# FPGA_HDMI_IN_OUT.net
KiCad netlist of a schematic drawn in Altium Designer
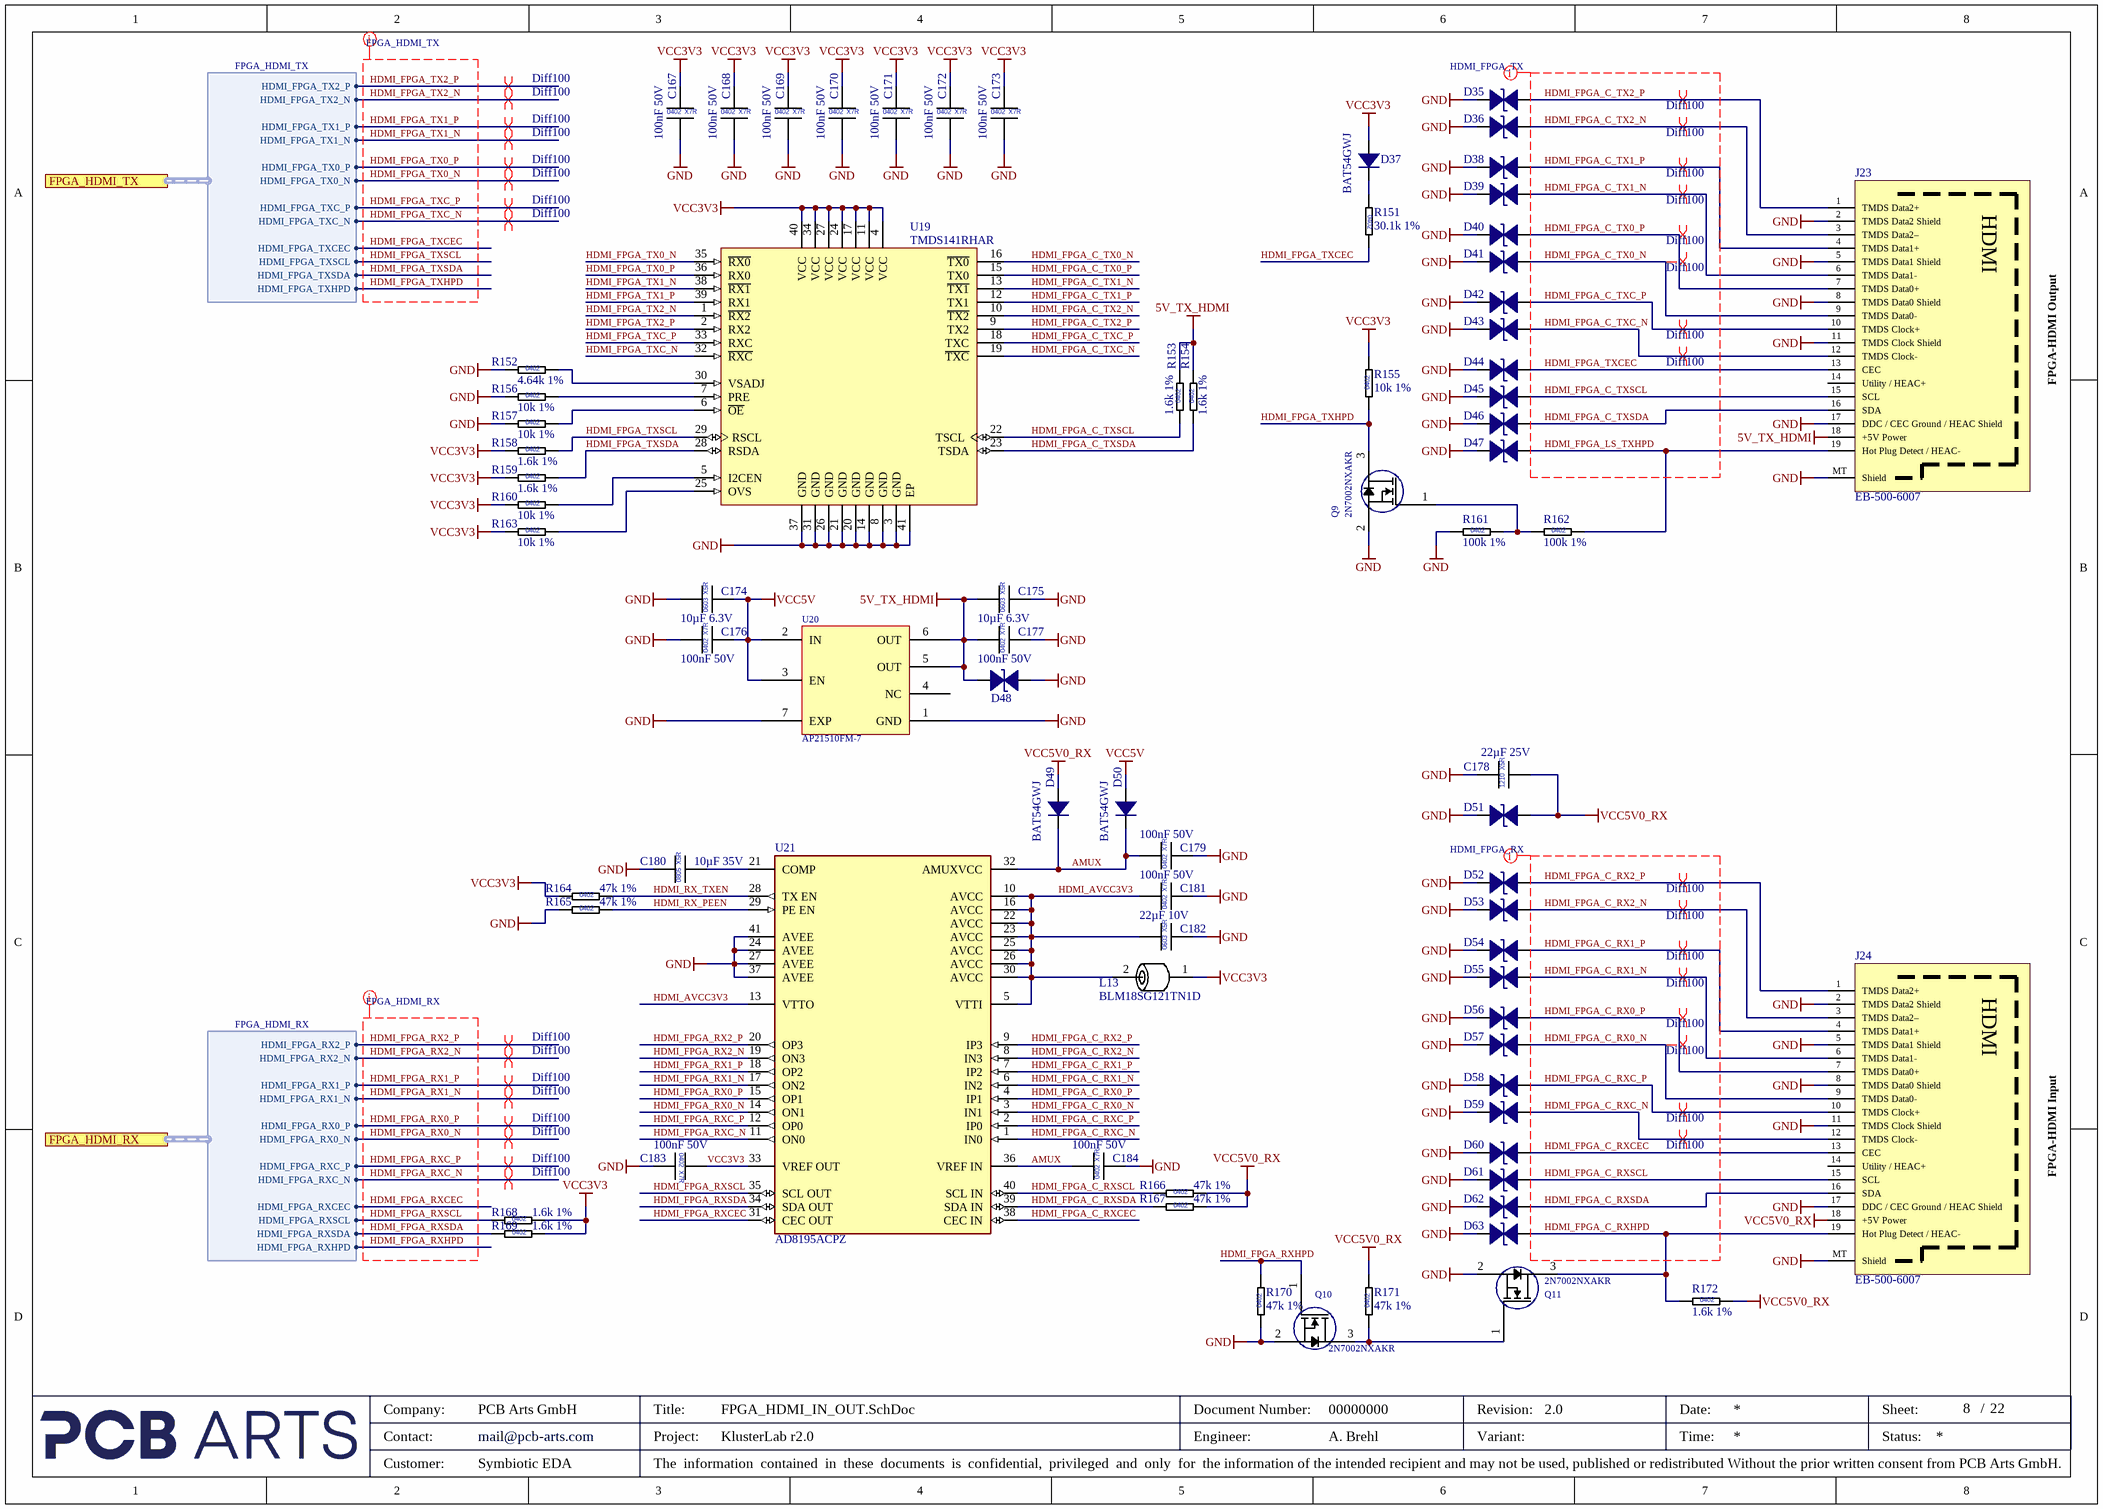
[diagram p0: FPGA_HDMI_IN_OUT.SchDoc]

(export (version "E")
  (design (tool "Eeschema 10.0.6"))
  (components
    (comp (ref "C167")
      (value "100nF 50V")
      (footprint "Cap:CAP_0402_L")
      (description "Multilayer Ceramic Capacitors MLCC - SMD/SMT 0402 50VDC")
      (libsource (lib "") (part "CAP_0402_100nF_50V_1"))
    )
    (comp (ref "C168")
      (value "100nF 50V")
      (footprint "Cap:CAP_0402_L")
      (description "Multilayer Ceramic Capacitors MLCC - SMD/SMT 0402 50VDC")
      (libsource (lib "") (part "CAP_0402_100nF_50V_1"))
    )
    (comp (ref "C169")
      (value "100nF 50V")
      (footprint "Cap:CAP_0402_L")
      (description "Multilayer Ceramic Capacitors MLCC - SMD/SMT 0402 50VDC")
      (libsource (lib "") (part "CAP_0402_100nF_50V_1"))
    )
    (comp (ref "C170")
      (value "100nF 50V")
      (footprint "Cap:CAP_0402_L")
      (description "Multilayer Ceramic Capacitors MLCC - SMD/SMT 0402 50VDC")
      (libsource (lib "") (part "CAP_0402_100nF_50V_1"))
    )
    (comp (ref "C171")
      (value "100nF 50V")
      (footprint "Cap:CAP_0402_L")
      (description "Multilayer Ceramic Capacitors MLCC - SMD/SMT 0402 50VDC")
      (libsource (lib "") (part "CAP_0402_100nF_50V_1"))
    )
    (comp (ref "C172")
      (value "100nF 50V")
      (footprint "Cap:CAP_0402_L")
      (description "Multilayer Ceramic Capacitors MLCC - SMD/SMT 0402 50VDC")
      (libsource (lib "") (part "CAP_0402_100nF_50V_1"))
    )
    (comp (ref "C173")
      (value "100nF 50V")
      (footprint "Cap:CAP_0402_L")
      (description "Multilayer Ceramic Capacitors MLCC - SMD/SMT 0402 50VDC")
      (libsource (lib "") (part "CAP_0402_100nF_50V_1"))
    )
    (comp (ref "C174")
      (value "10µF 6.3V")
      (footprint "Cap:CAP_0603_L")
      (description "Multilayer Ceramic Capacitors MLCC - SMD/SMT 0603 6.3VDC")
      (libsource (lib "Cap") (part "CAP_0603_10µF_6.3V"))
    )
    (comp (ref "C175")
      (value "10µF 6.3V")
      (footprint "Cap:CAP_0603_L")
      (description "Multilayer Ceramic Capacitors MLCC - SMD/SMT 0603 6.3VDC")
      (libsource (lib "Cap") (part "CAP_0603_10µF_6.3V"))
    )
    (comp (ref "C176")
      (value "100nF 50V")
      (footprint "Cap:CAP_0402_L")
      (description "Multilayer Ceramic Capacitors MLCC - SMD/SMT 0402 50VDC")
      (libsource (lib "Cap") (part "CAP_0402_100nF_50V"))
    )
    (comp (ref "C177")
      (value "100nF 50V")
      (footprint "Cap:CAP_0402_L")
      (description "Multilayer Ceramic Capacitors MLCC - SMD/SMT 0402 50VDC")
      (libsource (lib "Cap") (part "CAP_0402_100nF_50V"))
    )
    (comp (ref "C178")
      (value "22µF 25V")
      (footprint "Cap:CAP_1210")
      (description "Multilayer Ceramic Capacitors MLCC - SMD/SMT 1210 25VDC")
      (libsource (lib "Cap") (part "CAP_1210_22µF_25V"))
    )
    (comp (ref "C179")
      (value "100nF 50V")
      (footprint "Cap:CAP_0402_L")
      (description "Multilayer Ceramic Capacitors MLCC - SMD/SMT 0402 50VDC")
      (libsource (lib "Cap") (part "CAP_0402_100nF_50V"))
    )
    (comp (ref "C180")
      (value "10µF 35V")
      (footprint "Cap:CAP_0805")
      (description "Multilayer Ceramic Capacitors MLCC - SMD/SMT 0805 35VDC")
      (libsource (lib "Cap") (part "CAP_0805_10µF_35V"))
    )
    (comp (ref "C181")
      (value "100nF 50V")
      (footprint "Cap:CAP_0402_L")
      (description "Multilayer Ceramic Capacitors MLCC - SMD/SMT 0402 50VDC")
      (libsource (lib "Cap") (part "CAP_0402_100nF_50V"))
    )
    (comp (ref "C182")
      (value "22µF 10V")
      (footprint "Cap:CAP_0603_L")
      (description "Multilayer Ceramic Capacitors MLCC - SMD/SMT 0603 10VDC")
      (libsource (lib "Cap") (part "CAP_0603_22µF_10V"))
    )
    (comp (ref "C183")
      (value "100nF 50V")
      (footprint "Cap:CAP_0402_L")
      (description "Multilayer Ceramic Capacitors MLCC - SMD/SMT 0402 50VDC")
      (libsource (lib "") (part "CAP_0402_100nF_50V_1"))
    )
    (comp (ref "C184")
      (value "100nF 50V")
      (footprint "Cap:CAP_0402_L")
      (description "Multilayer Ceramic Capacitors MLCC - SMD/SMT 0402 50VDC")
      (libsource (lib "Cap") (part "CAP_0402_100nF_50V"))
    )
    (comp (ref "D35")
      (value "CESDP0402UC5VB")
      (footprint "Protec:TVS_0402")
      (description "Low Capacitance ESD Protection Diode 0402")
      (libsource (lib "Protec") (part "CESDP0402UC5VB_TVS Diode 0402"))
    )
    (comp (ref "D36")
      (value "CESDP0402UC5VB")
      (footprint "Protec:TVS_0402")
      (description "Low Capacitance ESD Protection Diode 0402")
      (libsource (lib "Protec") (part "CESDP0402UC5VB_TVS Diode 0402"))
    )
    (comp (ref "D37")
      (value "BAT54GWJ")
      (footprint "Active:SOD123")
      (description "Schottky Diode 30V, 200mA")
      (libsource (lib "Active") (part "BAT54GWJ_Schottky Diode 30V, 200mA"))
    )
    (comp (ref "D38")
      (value "CESDP0402UC5VB")
      (footprint "Protec:TVS_0402")
      (description "Low Capacitance ESD Protection Diode 0402")
      (libsource (lib "Protec") (part "CESDP0402UC5VB_TVS Diode 0402"))
    )
    (comp (ref "D39")
      (value "CESDP0402UC5VB")
      (footprint "Protec:TVS_0402")
      (description "Low Capacitance ESD Protection Diode 0402")
      (libsource (lib "Protec") (part "CESDP0402UC5VB_TVS Diode 0402"))
    )
    (comp (ref "D40")
      (value "CESDP0402UC5VB")
      (footprint "Protec:TVS_0402")
      (description "Low Capacitance ESD Protection Diode 0402")
      (libsource (lib "Protec") (part "CESDP0402UC5VB_TVS Diode 0402"))
    )
    (comp (ref "D41")
      (value "CESDP0402UC5VB")
      (footprint "Protec:TVS_0402")
      (description "Low Capacitance ESD Protection Diode 0402")
      (libsource (lib "Protec") (part "CESDP0402UC5VB_TVS Diode 0402"))
    )
    (comp (ref "D42")
      (value "CESDP0402UC5VB")
      (footprint "Protec:TVS_0402")
      (description "Low Capacitance ESD Protection Diode 0402")
      (libsource (lib "Protec") (part "CESDP0402UC5VB_TVS Diode 0402"))
    )
    (comp (ref "D43")
      (value "CESDP0402UC5VB")
      (footprint "Protec:TVS_0402")
      (description "Low Capacitance ESD Protection Diode 0402")
      (libsource (lib "Protec") (part "CESDP0402UC5VB_TVS Diode 0402"))
    )
    (comp (ref "D44")
      (value "CESDP0402UC5VB")
      (footprint "Protec:TVS_0402")
      (description "Low Capacitance ESD Protection Diode 0402")
      (libsource (lib "Protec") (part "CESDP0402UC5VB_TVS Diode 0402"))
    )
    (comp (ref "D45")
      (value "CESDP0402UC5VB")
      (footprint "Protec:TVS_0402")
      (description "Low Capacitance ESD Protection Diode 0402")
      (libsource (lib "Protec") (part "CESDP0402UC5VB_TVS Diode 0402"))
    )
    (comp (ref "D46")
      (value "CESDP0402UC5VB")
      (footprint "Protec:TVS_0402")
      (description "Low Capacitance ESD Protection Diode 0402")
      (libsource (lib "Protec") (part "CESDP0402UC5VB_TVS Diode 0402"))
    )
    (comp (ref "D47")
      (value "CESDP0402UC5VB")
      (footprint "Protec:TVS_0402")
      (description "Low Capacitance ESD Protection Diode 0402")
      (libsource (lib "Protec") (part "CESDP0402UC5VB_TVS Diode 0402"))
    )
    (comp (ref "D48")
      (value "CESDP0402UC5VB")
      (footprint "Protec:TVS_0402")
      (description "Low Capacitance ESD Protection Diode 0402")
      (libsource (lib "Protec") (part "CESDP0402UC5VB_TVS Diode 0402"))
    )
    (comp (ref "D49")
      (value "BAT54GWJ")
      (footprint "Active:SOD123")
      (description "Schottky Diode 30V, 200mA")
      (libsource (lib "Active") (part "BAT54GWJ_Schottky Diode 30V, 200mA"))
    )
    (comp (ref "D50")
      (value "BAT54GWJ")
      (footprint "Active:SOD123")
      (description "Schottky Diode 30V, 200mA")
      (libsource (lib "Active") (part "BAT54GWJ_Schottky Diode 30V, 200mA"))
    )
    (comp (ref "D51")
      (value "CESDP0402UC5VB")
      (footprint "Protec:TVS_0402")
      (description "Low Capacitance ESD Protection Diode 0402")
      (libsource (lib "Protec") (part "CESDP0402UC5VB_TVS Diode 0402"))
    )
    (comp (ref "D52")
      (value "CESDP0402UC5VB")
      (footprint "Protec:TVS_0402")
      (description "Low Capacitance ESD Protection Diode 0402")
      (libsource (lib "Protec") (part "CESDP0402UC5VB_TVS Diode 0402"))
    )
    (comp (ref "D53")
      (value "CESDP0402UC5VB")
      (footprint "Protec:TVS_0402")
      (description "Low Capacitance ESD Protection Diode 0402")
      (libsource (lib "Protec") (part "CESDP0402UC5VB_TVS Diode 0402"))
    )
    (comp (ref "D54")
      (value "CESDP0402UC5VB")
      (footprint "Protec:TVS_0402")
      (description "Low Capacitance ESD Protection Diode 0402")
      (libsource (lib "Protec") (part "CESDP0402UC5VB_TVS Diode 0402"))
    )
    (comp (ref "D55")
      (value "CESDP0402UC5VB")
      (footprint "Protec:TVS_0402")
      (description "Low Capacitance ESD Protection Diode 0402")
      (libsource (lib "Protec") (part "CESDP0402UC5VB_TVS Diode 0402"))
    )
    (comp (ref "D56")
      (value "CESDP0402UC5VB")
      (footprint "Protec:TVS_0402")
      (description "Low Capacitance ESD Protection Diode 0402")
      (libsource (lib "Protec") (part "CESDP0402UC5VB_TVS Diode 0402"))
    )
    (comp (ref "D57")
      (value "CESDP0402UC5VB")
      (footprint "Protec:TVS_0402")
      (description "Low Capacitance ESD Protection Diode 0402")
      (libsource (lib "Protec") (part "CESDP0402UC5VB_TVS Diode 0402"))
    )
    (comp (ref "D58")
      (value "CESDP0402UC5VB")
      (footprint "Protec:TVS_0402")
      (description "Low Capacitance ESD Protection Diode 0402")
      (libsource (lib "Protec") (part "CESDP0402UC5VB_TVS Diode 0402"))
    )
    (comp (ref "D59")
      (value "CESDP0402UC5VB")
      (footprint "Protec:TVS_0402")
      (description "Low Capacitance ESD Protection Diode 0402")
      (libsource (lib "Protec") (part "CESDP0402UC5VB_TVS Diode 0402"))
    )
    (comp (ref "D60")
      (value "CESDP0402UC5VB")
      (footprint "Protec:TVS_0402")
      (description "Low Capacitance ESD Protection Diode 0402")
      (libsource (lib "Protec") (part "CESDP0402UC5VB_TVS Diode 0402"))
    )
    (comp (ref "D61")
      (value "CESDP0402UC5VB")
      (footprint "Protec:TVS_0402")
      (description "Low Capacitance ESD Protection Diode 0402")
      (libsource (lib "Protec") (part "CESDP0402UC5VB_TVS Diode 0402"))
    )
    (comp (ref "D62")
      (value "CESDP0402UC5VB")
      (footprint "Protec:TVS_0402")
      (description "Low Capacitance ESD Protection Diode 0402")
      (libsource (lib "Protec") (part "CESDP0402UC5VB_TVS Diode 0402"))
    )
    (comp (ref "D63")
      (value "CESDP0402UC5VB")
      (footprint "Protec:TVS_0402")
      (description "Low Capacitance ESD Protection Diode 0402")
      (libsource (lib "Protec") (part "CESDP0402UC5VB_TVS Diode 0402"))
    )
    (comp (ref "J23")
      (value "EB-500-6007")
      (footprint "Conn:Elecbee EB-500-6007")
      (description "HDMI Connector Female Vertical 19 Pin")
      (libsource (lib "Conn") (part "EB-500-6007_HDMI Connector 19Pin Vertical THT"))
    )
    (comp (ref "J24")
      (value "EB-500-6007")
      (footprint "Conn:Elecbee EB-500-6007")
      (description "HDMI Connector Female Vertical 19 Pin")
      (libsource (lib "Conn") (part "EB-500-6007_HDMI Connector 19Pin Vertical THT"))
    )
    (comp (ref "L13")
      (value "BLM18SG121TN1D")
      (footprint "Indc:L_0603")
      (description "Ferritperlen BLM18_xN 0603 100MHz 120Ohm 3000mA 25mOhm RSER")
      (libsource (lib "Indc") (part "BLM18SG121TN1D_Ferrite Beads 0603 120Ohms 3000mA"))
    )
    (comp (ref "Q9")
      (value "2N7002NXAKR")
      (footprint "trans:SOT95P251X112-3N")
      (description "MOSFET 60V SGL N-CH TRENCHMOS")
      (libsource (lib "") (part "2N7002NXAKR_MOSFET 60V SGL N-CH TRENCHMOS_1"))
    )
    (comp (ref "Q10")
      (value "2N7002NXAKR")
      (footprint "trans:SOT95P251X112-3N")
      (description "MOSFET 60V SGL N-CH TRENCHMOS")
      (libsource (lib "") (part "2N7002NXAKR_MOSFET 60V SGL N-CH TRENCHMOS_1"))
    )
    (comp (ref "Q11")
      (value "2N7002NXAKR")
      (footprint "trans:SOT95P251X112-3N")
      (description "MOSFET 60V SGL N-CH TRENCHMOS")
      (libsource (lib "Trans") (part "2N7002NXAKR_MOSFET 60V SGL N-CH TRENCHMOS"))
    )
    (comp (ref "R151")
      (value "30.1k 1%")
      (footprint "Res:RES_0402_L")
      (description "Thick Film Resistors - SMD 30.1kOhm 1%")
      (libsource (lib "Res") (part "RES_0402_30.1k_1%"))
    )
    (comp (ref "R152")
      (value "4.64k 1%")
      (footprint "Res:RES_0402_L")
      (description "Thick Film Resistors - SMD 4.64kOhm 1%")
      (libsource (lib "Res") (part "RES_0402_4.64k_1%"))
    )
    (comp (ref "R153")
      (value "1.6k 1%")
      (footprint "Res:RES_0402_L")
      (description "Thick Film Resistors - SMD 1.6kOhm 1%")
      (libsource (lib "Res") (part "RES_0402_1.6k_1%"))
    )
    (comp (ref "R154")
      (value "1.6k 1%")
      (footprint "Res:RES_0402_L")
      (description "Thick Film Resistors - SMD 1.6kOhm 1%")
      (libsource (lib "Res") (part "RES_0402_1.6k_1%"))
    )
    (comp (ref "R155")
      (value "10k 1%")
      (footprint "Res:RES_0402_L")
      (description "Thick Film Resistors - SMD 10kOhm 1%")
      (libsource (lib "Res") (part "RES_0402_10k_1%"))
    )
    (comp (ref "R156")
      (value "10k 1%")
      (footprint "Res:RES_0402_L")
      (description "Thick Film Resistors - SMD 10kOhm 1%")
      (libsource (lib "Res") (part "RES_0402_10k_1%"))
    )
    (comp (ref "R157")
      (value "10k 1%")
      (footprint "Res:RES_0402_L")
      (description "Thick Film Resistors - SMD 10kOhm 1%")
      (libsource (lib "Res") (part "RES_0402_10k_1%"))
    )
    (comp (ref "R158")
      (value "1.6k 1%")
      (footprint "Res:RES_0402_L")
      (description "Thick Film Resistors - SMD 1.6kOhm 1%")
      (libsource (lib "Res") (part "RES_0402_1.6k_1%"))
    )
    (comp (ref "R159")
      (value "1.6k 1%")
      (footprint "Res:RES_0402_L")
      (description "Thick Film Resistors - SMD 1.6kOhm 1%")
      (libsource (lib "Res") (part "RES_0402_1.6k_1%"))
    )
    (comp (ref "R160")
      (value "10k 1%")
      (footprint "Res:RES_0402_L")
      (description "Thick Film Resistors - SMD 10kOhm 1%")
      (libsource (lib "Res") (part "RES_0402_10k_1%"))
    )
    (comp (ref "R161")
      (value "100k 1%")
      (footprint "Res:RES_0402_L")
      (description "Thick Film Resistors - SMD 100kOhm 1%")
      (libsource (lib "Res") (part "RES_0402_100k_1%"))
    )
    (comp (ref "R162")
      (value "100k 1%")
      (footprint "Res:RES_0402_L")
      (description "Thick Film Resistors - SMD 100kOhm 1%")
      (libsource (lib "Res") (part "RES_0402_100k_1%"))
    )
    (comp (ref "R163")
      (value "10k 1%")
      (footprint "Res:RES_0402_L")
      (description "Thick Film Resistors - SMD 10kOhm 1%")
      (libsource (lib "Res") (part "RES_0402_10k_1%"))
    )
    (comp (ref "R164")
      (value "47k 1%")
      (footprint "Res:RES_0402_L")
      (description "Thick Film Resistors - SMD 47kOhm 1%")
      (libsource (lib "Res") (part "RES_0402_47k_1%"))
    )
    (comp (ref "R165")
      (value "47k 1%")
      (footprint "Res:RES_0402_L")
      (description "Thick Film Resistors - SMD 47kOhm 1%")
      (libsource (lib "Res") (part "RES_0402_47k_1%"))
    )
    (comp (ref "R166")
      (value "47k 1%")
      (footprint "Res:RES_0402_L")
      (description "Thick Film Resistors - SMD 47kOhm 1%")
      (libsource (lib "Res") (part "RES_0402_47k_1%"))
    )
    (comp (ref "R167")
      (value "47k 1%")
      (footprint "Res:RES_0402_L")
      (description "Thick Film Resistors - SMD 47kOhm 1%")
      (libsource (lib "Res") (part "RES_0402_47k_1%"))
    )
    (comp (ref "R168")
      (value "1.6k 1%")
      (footprint "Res:RES_0402_L")
      (description "Thick Film Resistors - SMD 1.6kOhm 1%")
      (libsource (lib "Res") (part "RES_0402_1.6k_1%"))
    )
    (comp (ref "R169")
      (value "1.6k 1%")
      (footprint "Res:RES_0402_L")
      (description "Thick Film Resistors - SMD 1.6kOhm 1%")
      (libsource (lib "Res") (part "RES_0402_1.6k_1%"))
    )
    (comp (ref "R170")
      (value "47k 1%")
      (footprint "Res:RES_0402_L")
      (description "Thick Film Resistors - SMD 47kOhm 1%")
      (libsource (lib "Res") (part "RES_0402_47k_1%"))
    )
    (comp (ref "R171")
      (value "47k 1%")
      (footprint "Res:RES_0402_L")
      (description "Thick Film Resistors - SMD 47kOhm 1%")
      (libsource (lib "Res") (part "RES_0402_47k_1%"))
    )
    (comp (ref "R172")
      (value "1.6k 1%")
      (footprint "Res:RES_0402_L")
      (description "Thick Film Resistors - SMD 1.6kOhm 1%")
      (libsource (lib "Res") (part "RES_0402_1.6k_1%"))
    )
    (comp (ref "U19")
      (value "TMDS141RHAR")
      (footprint "Digital:QFN50P600X600X100-41N")
      (description "HDMI Hider, 130 mA, 6 kV, 0 to +70 degC, 40-pin QFN")
      (libsource (lib "Digital") (part "TMDS141RHAR_HDMI Hider, 130 mA, 6 kV, 0 to +70 degC, 40-pin QFN"))
    )
    (comp (ref "U20")
      (value "AP21510FM-7")
      (footprint "Power:QFN50P201X181X60_HS-7N")
      (description "Power Switch ICs - Power Distribution 0.5A SGL Ch USB 2.0 Curr Limited Switch")
      (libsource (lib "Power") (part "AP21510FM-7_Power Switch ICs - Power Distribution Load Switch"))
    )
    (comp (ref "U21")
      (value "AD8195ACPZ")
      (footprint "Digital:QFN50P600X600X100-41N")
      (description "IC VIDEO HDMI/DVI BUFFER 40LFCSP")
      (libsource (lib "Digital") (part "AD8195ACPZ_IC VIDEO HDMI/DVI BUFFER 40LFCSP"))
    )
  )
  (nets
    (net (code "3") (name "/AMUX") (class "Default")
      (node (ref "C179") (pin "1") (pinfunction "1_1") (pintype "passive"))
      (node (ref "C184") (pin "1") (pinfunction "1_1") (pintype "passive"))
      (node (ref "D49") (pin "1") (pinfunction "1_1") (pintype "passive"))
      (node (ref "D50") (pin "1") (pinfunction "1_1") (pintype "passive"))
      (node (ref "U21") (pin "32") (pinfunction "AMUXVCC_32") (pintype "power_in"))
      (node (ref "U21") (pin "36") (pinfunction "VREF_IN_36") (pintype "passive"))
    )
    (net (code "4") (name "/HDMI_AVCC3V3") (class "Default")
      (node (ref "C181") (pin "1") (pinfunction "1_1") (pintype "passive"))
      (node (ref "C182") (pin "1") (pinfunction "1_1") (pintype "passive"))
      (node (ref "L13") (pin "2") (pinfunction "2_2") (pintype "passive"))
      (node (ref "U21") (pin "10") (pinfunction "AVCC_10") (pintype "power_in"))
      (node (ref "U21") (pin "13") (pinfunction "VTTO_13") (pintype "power_in"))
      (node (ref "U21") (pin "16") (pinfunction "AVCC_16") (pintype "power_in"))
      (node (ref "U21") (pin "22") (pinfunction "AVCC_22") (pintype "power_in"))
      (node (ref "U21") (pin "23") (pinfunction "AVCC_23") (pintype "power_in"))
      (node (ref "U21") (pin "25") (pinfunction "AVCC_25") (pintype "power_in"))
      (node (ref "U21") (pin "26") (pinfunction "AVCC_26") (pintype "power_in"))
      (node (ref "U21") (pin "30") (pinfunction "AVCC_30") (pintype "power_in"))
      (node (ref "U21") (pin "5") (pinfunction "VTTI_5") (pintype "power_in"))
    )
    (net (code "5") (name "/HDMI_FPGA_C_RX0_N") (class "Default")
      (node (ref "D57") (pin "2") (pinfunction "2_2") (pintype "passive"))
      (node (ref "J24") (pin "9") (pinfunction "TMDS_Data0-_9") (pintype "passive"))
      (node (ref "U21") (pin "3") (pinfunction "IN1_3") (pintype "input"))
    )
    (net (code "6") (name "/HDMI_FPGA_C_RX0_P") (class "Default")
      (node (ref "D56") (pin "2") (pinfunction "2_2") (pintype "passive"))
      (node (ref "J24") (pin "7") (pinfunction "TMDS_Data0+_7") (pintype "passive"))
      (node (ref "U21") (pin "4") (pinfunction "IP1_4") (pintype "input"))
    )
    (net (code "7") (name "/HDMI_FPGA_C_RX1_N") (class "Default")
      (node (ref "D55") (pin "2") (pinfunction "2_2") (pintype "passive"))
      (node (ref "J24") (pin "6") (pinfunction "TMDS_Data1-_6") (pintype "passive"))
      (node (ref "U21") (pin "6") (pinfunction "IN2_6") (pintype "input"))
    )
    (net (code "8") (name "/HDMI_FPGA_C_RX1_P") (class "Default")
      (node (ref "D54") (pin "2") (pinfunction "2_2") (pintype "passive"))
      (node (ref "J24") (pin "4") (pinfunction "TMDS_Data1+_4") (pintype "passive"))
      (node (ref "U21") (pin "7") (pinfunction "IP2_7") (pintype "input"))
    )
    (net (code "9") (name "/HDMI_FPGA_C_RX2_N") (class "Default")
      (node (ref "D53") (pin "2") (pinfunction "2_2") (pintype "passive"))
      (node (ref "J24") (pin "3") (pinfunction "TMDS_Data2–_3") (pintype "passive"))
      (node (ref "U21") (pin "8") (pinfunction "IN3_8") (pintype "input"))
    )
    (net (code "10") (name "/HDMI_FPGA_C_RX2_P") (class "Default")
      (node (ref "D52") (pin "2") (pinfunction "2_2") (pintype "passive"))
      (node (ref "J24") (pin "1") (pinfunction "TMDS_Data2+_1") (pintype "passive"))
      (node (ref "U21") (pin "9") (pinfunction "IP3_9") (pintype "input"))
    )
    (net (code "11") (name "/HDMI_FPGA_C_RXCEC") (class "Default")
      (node (ref "D60") (pin "2") (pinfunction "2_2") (pintype "passive"))
      (node (ref "J24") (pin "13") (pinfunction "CEC_13") (pintype "passive"))
      (node (ref "U21") (pin "38") (pinfunction "CEC_IN_38") (pintype "bidirectional"))
    )
    (net (code "12") (name "/HDMI_FPGA_C_RXC_N") (class "Default")
      (node (ref "D59") (pin "2") (pinfunction "2_2") (pintype "passive"))
      (node (ref "J24") (pin "12") (pinfunction "TMDS_Clock-_12") (pintype "passive"))
      (node (ref "U21") (pin "1") (pinfunction "IN0_1") (pintype "input"))
    )
    (net (code "13") (name "/HDMI_FPGA_C_RXC_P") (class "Default")
      (node (ref "D58") (pin "2") (pinfunction "2_2") (pintype "passive"))
      (node (ref "J24") (pin "10") (pinfunction "TMDS_Clock+_10") (pintype "passive"))
      (node (ref "U21") (pin "2") (pinfunction "IP0_2") (pintype "input"))
    )
    (net (code "14") (name "/HDMI_FPGA_C_RXHPD") (class "Default")
      (node (ref "D63") (pin "2") (pinfunction "2_2") (pintype "passive"))
      (node (ref "J24") (pin "19") (pinfunction "Hot_Plug_Detect_/_HEAC-_19") (pintype "passive"))
      (node (ref "Q11") (pin "3") (pinfunction "D_3") (pintype "passive"))
      (node (ref "R172") (pin "1") (pinfunction "1_1") (pintype "passive"))
    )
    (net (code "15") (name "/HDMI_FPGA_C_RXSCL") (class "Default")
      (node (ref "D61") (pin "2") (pinfunction "2_2") (pintype "passive"))
      (node (ref "J24") (pin "15") (pinfunction "SCL_15") (pintype "passive"))
      (node (ref "R166") (pin "1") (pinfunction "1_1") (pintype "passive"))
      (node (ref "U21") (pin "40") (pinfunction "SCL_IN_40") (pintype "bidirectional"))
    )
    (net (code "16") (name "/HDMI_FPGA_C_RXSDA") (class "Default")
      (node (ref "D62") (pin "2") (pinfunction "2_2") (pintype "passive"))
      (node (ref "J24") (pin "16") (pinfunction "SDA_16") (pintype "passive"))
      (node (ref "R167") (pin "1") (pinfunction "1_1") (pintype "passive"))
      (node (ref "U21") (pin "39") (pinfunction "SDA_IN_39") (pintype "bidirectional"))
    )
    (net (code "17") (name "/HDMI_FPGA_C_TX0_N") (class "Default")
      (node (ref "D41") (pin "2") (pinfunction "2_2") (pintype "passive"))
      (node (ref "J23") (pin "9") (pinfunction "TMDS_Data0-_9") (pintype "passive"))
      (node (ref "U19") (pin "16") (pinfunction "~{TX0}_16") (pintype "tri_state"))
    )
    (net (code "18") (name "/HDMI_FPGA_C_TX0_P") (class "Default")
      (node (ref "D40") (pin "2") (pinfunction "2_2") (pintype "passive"))
      (node (ref "J23") (pin "7") (pinfunction "TMDS_Data0+_7") (pintype "passive"))
      (node (ref "U19") (pin "15") (pinfunction "TX0_15") (pintype "tri_state"))
    )
    (net (code "19") (name "/HDMI_FPGA_C_TX1_N") (class "Default")
      (node (ref "D39") (pin "2") (pinfunction "2_2") (pintype "passive"))
      (node (ref "J23") (pin "6") (pinfunction "TMDS_Data1-_6") (pintype "passive"))
      (node (ref "U19") (pin "13") (pinfunction "~{TX1}_13") (pintype "tri_state"))
    )
    (net (code "20") (name "/HDMI_FPGA_C_TX1_P") (class "Default")
      (node (ref "D38") (pin "2") (pinfunction "2_2") (pintype "passive"))
      (node (ref "J23") (pin "4") (pinfunction "TMDS_Data1+_4") (pintype "passive"))
      (node (ref "U19") (pin "12") (pinfunction "TX1_12") (pintype "tri_state"))
    )
    (net (code "21") (name "/HDMI_FPGA_C_TX2_N") (class "Default")
      (node (ref "D36") (pin "2") (pinfunction "2_2") (pintype "passive"))
      (node (ref "J23") (pin "3") (pinfunction "TMDS_Data2–_3") (pintype "passive"))
      (node (ref "U19") (pin "10") (pinfunction "~{TX2}_10") (pintype "tri_state"))
    )
    (net (code "22") (name "/HDMI_FPGA_C_TX2_P") (class "Default")
      (node (ref "D35") (pin "2") (pinfunction "2_2") (pintype "passive"))
      (node (ref "J23") (pin "1") (pinfunction "TMDS_Data2+_1") (pintype "passive"))
      (node (ref "U19") (pin "9") (pinfunction "TX2_9") (pintype "tri_state"))
    )
    (net (code "23") (name "/HDMI_FPGA_C_TXC_N") (class "Default")
      (node (ref "D43") (pin "2") (pinfunction "2_2") (pintype "passive"))
      (node (ref "J23") (pin "12") (pinfunction "TMDS_Clock-_12") (pintype "passive"))
      (node (ref "U19") (pin "19") (pinfunction "~{TXC}_19") (pintype "tri_state"))
    )
    (net (code "24") (name "/HDMI_FPGA_C_TXC_P") (class "Default")
      (node (ref "D42") (pin "2") (pinfunction "2_2") (pintype "passive"))
      (node (ref "J23") (pin "10") (pinfunction "TMDS_Clock+_10") (pintype "passive"))
      (node (ref "U19") (pin "18") (pinfunction "TXC_18") (pintype "tri_state"))
    )
    (net (code "25") (name "/HDMI_FPGA_C_TXSCL") (class "Default")
      (node (ref "D45") (pin "2") (pinfunction "2_2") (pintype "passive"))
      (node (ref "J23") (pin "15") (pinfunction "SCL_15") (pintype "passive"))
      (node (ref "R153") (pin "1") (pinfunction "1_1") (pintype "passive"))
      (node (ref "U19") (pin "22") (pinfunction "TSCL_22") (pintype "bidirectional"))
    )
    (net (code "26") (name "/HDMI_FPGA_C_TXSDA") (class "Default")
      (node (ref "D46") (pin "2") (pinfunction "2_2") (pintype "passive"))
      (node (ref "J23") (pin "16") (pinfunction "SDA_16") (pintype "passive"))
      (node (ref "R154") (pin "1") (pinfunction "1_1") (pintype "passive"))
      (node (ref "U19") (pin "23") (pinfunction "TSDA_23") (pintype "bidirectional"))
    )
    (net (code "27") (name "/HDMI_FPGA_LS_TXHPD") (class "Default")
      (node (ref "D47") (pin "2") (pinfunction "2_2") (pintype "passive"))
      (node (ref "J23") (pin "19") (pinfunction "Hot_Plug_Detect_/_HEAC-_19") (pintype "passive"))
      (node (ref "R162") (pin "2") (pinfunction "2_2") (pintype "passive"))
    )
    (net (code "28") (name "/HDMI_FPGA_RX0_N") (class "Default")
      (node (ref "U21") (pin "14") (pinfunction "ON1_14") (pintype "output"))
    )
    (net (code "29") (name "/HDMI_FPGA_RX0_P") (class "Default")
      (node (ref "U21") (pin "15") (pinfunction "OP1_15") (pintype "output"))
    )
    (net (code "30") (name "/HDMI_FPGA_RX1_N") (class "Default")
      (node (ref "U21") (pin "17") (pinfunction "ON2_17") (pintype "output"))
    )
    (net (code "31") (name "/HDMI_FPGA_RX1_P") (class "Default")
      (node (ref "U21") (pin "18") (pinfunction "OP2_18") (pintype "output"))
    )
    (net (code "32") (name "/HDMI_FPGA_RX2_N") (class "Default")
      (node (ref "U21") (pin "19") (pinfunction "ON3_19") (pintype "output"))
    )
    (net (code "33") (name "/HDMI_FPGA_RX2_P") (class "Default")
      (node (ref "U21") (pin "20") (pinfunction "OP3_20") (pintype "output"))
    )
    (net (code "34") (name "/HDMI_FPGA_RXCEC") (class "Default")
      (node (ref "U21") (pin "31") (pinfunction "CEC_OUT_31") (pintype "bidirectional"))
    )
    (net (code "35") (name "/HDMI_FPGA_RXC_N") (class "Default")
      (node (ref "U21") (pin "11") (pinfunction "ON0_11") (pintype "output"))
    )
    (net (code "36") (name "/HDMI_FPGA_RXC_P") (class "Default")
      (node (ref "U21") (pin "12") (pinfunction "OP0_12") (pintype "output"))
    )
    (net (code "37") (name "/HDMI_FPGA_RXHPD") (class "Default")
      (node (ref "Q10") (pin "1") (pinfunction "G_1") (pintype "passive"))
      (node (ref "R170") (pin "2") (pinfunction "2_2") (pintype "passive"))
    )
    (net (code "38") (name "/HDMI_FPGA_RXSCL") (class "Default")
      (node (ref "R168") (pin "1") (pinfunction "1_1") (pintype "passive"))
      (node (ref "U21") (pin "35") (pinfunction "SCL_OUT_35") (pintype "bidirectional"))
    )
    (net (code "39") (name "/HDMI_FPGA_RXSDA") (class "Default")
      (node (ref "R169") (pin "1") (pinfunction "1_1") (pintype "passive"))
      (node (ref "U21") (pin "34") (pinfunction "SDA_OUT_34") (pintype "bidirectional"))
    )
    (net (code "40") (name "/HDMI_FPGA_TX0_N") (class "Default")
      (node (ref "U19") (pin "35") (pinfunction "~{RX0}_35") (pintype "input"))
    )
    (net (code "41") (name "/HDMI_FPGA_TX0_P") (class "Default")
      (node (ref "U19") (pin "36") (pinfunction "RX0_36") (pintype "input"))
    )
    (net (code "42") (name "/HDMI_FPGA_TX1_N") (class "Default")
      (node (ref "U19") (pin "38") (pinfunction "~{RX1}_38") (pintype "input"))
    )
    (net (code "43") (name "/HDMI_FPGA_TX1_P") (class "Default")
      (node (ref "U19") (pin "39") (pinfunction "RX1_39") (pintype "input"))
    )
    (net (code "44") (name "/HDMI_FPGA_TX2_N") (class "Default")
      (node (ref "U19") (pin "1") (pinfunction "~{RX2}_1") (pintype "input"))
    )
    (net (code "45") (name "/HDMI_FPGA_TX2_P") (class "Default")
      (node (ref "U19") (pin "2") (pinfunction "RX2_2") (pintype "input"))
    )
    (net (code "46") (name "/HDMI_FPGA_TXCEC") (class "Default")
      (node (ref "D44") (pin "2") (pinfunction "2_2") (pintype "passive"))
      (node (ref "J23") (pin "13") (pinfunction "CEC_13") (pintype "passive"))
      (node (ref "R151") (pin "2") (pinfunction "2_2") (pintype "passive"))
    )
    (net (code "47") (name "/HDMI_FPGA_TXC_N") (class "Default")
      (node (ref "U19") (pin "32") (pinfunction "~{RXC}_32") (pintype "input"))
    )
    (net (code "48") (name "/HDMI_FPGA_TXC_P") (class "Default")
      (node (ref "U19") (pin "33") (pinfunction "RXC_33") (pintype "input"))
    )
    (net (code "49") (name "/HDMI_FPGA_TXHPD") (class "Default")
      (node (ref "Q9") (pin "3") (pinfunction "D_3") (pintype "passive"))
      (node (ref "R155") (pin "1") (pinfunction "1_1") (pintype "passive"))
    )
    (net (code "50") (name "/HDMI_FPGA_TXSCL") (class "Default")
      (node (ref "R158") (pin "2") (pinfunction "2_2") (pintype "passive"))
      (node (ref "U19") (pin "29") (pinfunction "RSCL_29") (pintype "bidirectional"))
    )
    (net (code "51") (name "/HDMI_FPGA_TXSDA") (class "Default")
      (node (ref "R159") (pin "2") (pinfunction "2_2") (pintype "passive"))
      (node (ref "U19") (pin "28") (pinfunction "RSDA_28") (pintype "bidirectional"))
    )
    (net (code "52") (name "/HDMI_RX_PEEN") (class "Default")
      (node (ref "R165") (pin "2") (pinfunction "2_2") (pintype "passive"))
      (node (ref "U21") (pin "29") (pinfunction "PE_EN_29") (pintype "input"))
    )
    (net (code "53") (name "/HDMI_RX_TXEN") (class "Default")
      (node (ref "R164") (pin "2") (pinfunction "2_2") (pintype "passive"))
      (node (ref "U21") (pin "28") (pinfunction "TX_EN_28") (pintype "output"))
    )
    (net (code "56") (name "5V_TX_HDMI") (class "Default")
      (node (ref "C175") (pin "1") (pinfunction "1_1") (pintype "passive"))
      (node (ref "C177") (pin "1") (pinfunction "1_1") (pintype "passive"))
      (node (ref "D48") (pin "1") (pinfunction "1_1") (pintype "passive"))
      (node (ref "J23") (pin "18") (pinfunction "+5V_Power_18") (pintype "passive"))
      (node (ref "R153") (pin "2") (pinfunction "2_2") (pintype "passive"))
      (node (ref "R154") (pin "2") (pinfunction "2_2") (pintype "passive"))
      (node (ref "U20") (pin "5") (pinfunction "OUT_5") (pintype "power_in"))
      (node (ref "U20") (pin "6") (pinfunction "OUT_6") (pintype "power_in"))
    )
    (net (code "57") (name "GND") (class "Default")
      (node (ref "C167") (pin "2") (pinfunction "2_2") (pintype "passive"))
      (node (ref "C168") (pin "2") (pinfunction "2_2") (pintype "passive"))
      (node (ref "C169") (pin "2") (pinfunction "2_2") (pintype "passive"))
      (node (ref "C170") (pin "2") (pinfunction "2_2") (pintype "passive"))
      (node (ref "C171") (pin "2") (pinfunction "2_2") (pintype "passive"))
      (node (ref "C172") (pin "2") (pinfunction "2_2") (pintype "passive"))
      (node (ref "C173") (pin "2") (pinfunction "2_2") (pintype "passive"))
      (node (ref "C174") (pin "1") (pinfunction "1_1") (pintype "passive"))
      (node (ref "C175") (pin "2") (pinfunction "2_2") (pintype "passive"))
      (node (ref "C176") (pin "1") (pinfunction "1_1") (pintype "passive"))
      (node (ref "C177") (pin "2") (pinfunction "2_2") (pintype "passive"))
      (node (ref "C178") (pin "1") (pinfunction "1_1") (pintype "passive"))
      (node (ref "C179") (pin "2") (pinfunction "2_2") (pintype "passive"))
      (node (ref "C180") (pin "1") (pinfunction "1_1") (pintype "passive"))
      (node (ref "C181") (pin "2") (pinfunction "2_2") (pintype "passive"))
      (node (ref "C182") (pin "2") (pinfunction "2_2") (pintype "passive"))
      (node (ref "C183") (pin "2") (pinfunction "2_2") (pintype "passive"))
      (node (ref "C184") (pin "2") (pinfunction "2_2") (pintype "passive"))
      (node (ref "D35") (pin "1") (pinfunction "1_1") (pintype "passive"))
      (node (ref "D36") (pin "1") (pinfunction "1_1") (pintype "passive"))
      (node (ref "D38") (pin "1") (pinfunction "1_1") (pintype "passive"))
      (node (ref "D39") (pin "1") (pinfunction "1_1") (pintype "passive"))
      (node (ref "D40") (pin "1") (pinfunction "1_1") (pintype "passive"))
      (node (ref "D41") (pin "1") (pinfunction "1_1") (pintype "passive"))
      (node (ref "D42") (pin "1") (pinfunction "1_1") (pintype "passive"))
      (node (ref "D43") (pin "1") (pinfunction "1_1") (pintype "passive"))
      (node (ref "D44") (pin "1") (pinfunction "1_1") (pintype "passive"))
      (node (ref "D45") (pin "1") (pinfunction "1_1") (pintype "passive"))
      (node (ref "D46") (pin "1") (pinfunction "1_1") (pintype "passive"))
      (node (ref "D47") (pin "1") (pinfunction "1_1") (pintype "passive"))
      (node (ref "D48") (pin "2") (pinfunction "2_2") (pintype "passive"))
      (node (ref "D51") (pin "1") (pinfunction "1_1") (pintype "passive"))
      (node (ref "D52") (pin "1") (pinfunction "1_1") (pintype "passive"))
      (node (ref "D53") (pin "1") (pinfunction "1_1") (pintype "passive"))
      (node (ref "D54") (pin "1") (pinfunction "1_1") (pintype "passive"))
      (node (ref "D55") (pin "1") (pinfunction "1_1") (pintype "passive"))
      (node (ref "D56") (pin "1") (pinfunction "1_1") (pintype "passive"))
      (node (ref "D57") (pin "1") (pinfunction "1_1") (pintype "passive"))
      (node (ref "D58") (pin "1") (pinfunction "1_1") (pintype "passive"))
      (node (ref "D59") (pin "1") (pinfunction "1_1") (pintype "passive"))
      (node (ref "D60") (pin "1") (pinfunction "1_1") (pintype "passive"))
      (node (ref "D61") (pin "1") (pinfunction "1_1") (pintype "passive"))
      (node (ref "D62") (pin "1") (pinfunction "1_1") (pintype "passive"))
      (node (ref "D63") (pin "1") (pinfunction "1_1") (pintype "passive"))
      (node (ref "J23") (pin "11") (pinfunction "TMDS_Clock_Shield_11") (pintype "passive"))
      (node (ref "J23") (pin "17") (pinfunction "DDC_/_CEC_Ground_/_HEAC_Shield_17") (pintype "passive"))
      (node (ref "J23") (pin "2") (pinfunction "TMDS_Data2_Shield_2") (pintype "passive"))
      (node (ref "J23") (pin "5") (pinfunction "TMDS_Data1_Shield_5") (pintype "passive"))
      (node (ref "J23") (pin "8") (pinfunction "TMDS_Data0_Shield_8") (pintype "passive"))
      (node (ref "J23") (pin "MT") (pinfunction "Shield_MT") (pintype "passive"))
      (node (ref "J24") (pin "11") (pinfunction "TMDS_Clock_Shield_11") (pintype "passive"))
      (node (ref "J24") (pin "17") (pinfunction "DDC_/_CEC_Ground_/_HEAC_Shield_17") (pintype "passive"))
      (node (ref "J24") (pin "2") (pinfunction "TMDS_Data2_Shield_2") (pintype "passive"))
      (node (ref "J24") (pin "5") (pinfunction "TMDS_Data1_Shield_5") (pintype "passive"))
      (node (ref "J24") (pin "8") (pinfunction "TMDS_Data0_Shield_8") (pintype "passive"))
      (node (ref "J24") (pin "MT") (pinfunction "Shield_MT") (pintype "passive"))
      (node (ref "Q10") (pin "2") (pinfunction "S_2") (pintype "passive"))
      (node (ref "Q11") (pin "2") (pinfunction "S_2") (pintype "passive"))
      (node (ref "Q9") (pin "2") (pinfunction "S_2") (pintype "passive"))
      (node (ref "R152") (pin "1") (pinfunction "1_1") (pintype "passive"))
      (node (ref "R156") (pin "1") (pinfunction "1_1") (pintype "passive"))
      (node (ref "R157") (pin "1") (pinfunction "1_1") (pintype "passive"))
      (node (ref "R161") (pin "1") (pinfunction "1_1") (pintype "passive"))
      (node (ref "R165") (pin "1") (pinfunction "1_1") (pintype "passive"))
      (node (ref "R170") (pin "1") (pinfunction "1_1") (pintype "passive"))
      (node (ref "U19") (pin "14") (pinfunction "GND_14") (pintype "power_in"))
      (node (ref "U19") (pin "20") (pinfunction "GND_20") (pintype "power_in"))
      (node (ref "U19") (pin "21") (pinfunction "GND_21") (pintype "power_in"))
      (node (ref "U19") (pin "26") (pinfunction "GND_26") (pintype "power_in"))
      (node (ref "U19") (pin "3") (pinfunction "GND_3") (pintype "power_in"))
      (node (ref "U19") (pin "31") (pinfunction "GND_31") (pintype "power_in"))
      (node (ref "U19") (pin "37") (pinfunction "GND_37") (pintype "power_in"))
      (node (ref "U19") (pin "41") (pinfunction "EP_41") (pintype "power_in"))
      (node (ref "U19") (pin "8") (pinfunction "GND_8") (pintype "power_in"))
      (node (ref "U20") (pin "1") (pinfunction "GND_1") (pintype "power_in"))
      (node (ref "U20") (pin "7") (pinfunction "EXP_7") (pintype "power_in"))
      (node (ref "U21") (pin "24") (pinfunction "AVEE_24") (pintype "power_in"))
      (node (ref "U21") (pin "27") (pinfunction "AVEE_27") (pintype "power_in"))
      (node (ref "U21") (pin "37") (pinfunction "AVEE_37") (pintype "power_in"))
      (node (ref "U21") (pin "41") (pinfunction "AVEE_41") (pintype "power_in"))
    )
    (net (code "58") (name "Net-(D37-Pad1)") (class "Default")
      (node (ref "D37") (pin "1") (pinfunction "1_1") (pintype "passive"))
      (node (ref "R151") (pin "1") (pinfunction "1_1") (pintype "passive"))
    )
    (net (code "59") (name "Net-(Q9-G)") (class "Default")
      (node (ref "Q9") (pin "1") (pinfunction "G_1") (pintype "passive"))
      (node (ref "R161") (pin "2") (pinfunction "2_2") (pintype "passive"))
      (node (ref "R162") (pin "1") (pinfunction "1_1") (pintype "passive"))
    )
    (net (code "60") (name "Net-(Q10-D)") (class "Default")
      (node (ref "Q10") (pin "3") (pinfunction "D_3") (pintype "passive"))
      (node (ref "Q11") (pin "1") (pinfunction "G_1") (pintype "passive"))
      (node (ref "R171") (pin "1") (pinfunction "1_1") (pintype "passive"))
    )
    (net (code "61") (name "Net-(U19-I2CEN)") (class "Default")
      (node (ref "R160") (pin "2") (pinfunction "2_2") (pintype "passive"))
      (node (ref "U19") (pin "5") (pinfunction "I2CEN_5") (pintype "input"))
    )
    (net (code "62") (name "Net-(U19-OVS)") (class "Default")
      (node (ref "R163") (pin "2") (pinfunction "2_2") (pintype "passive"))
      (node (ref "U19") (pin "25") (pinfunction "OVS_25") (pintype "input"))
    )
    (net (code "63") (name "Net-(U19-PRE)") (class "Default")
      (node (ref "R156") (pin "2") (pinfunction "2_2") (pintype "passive"))
      (node (ref "U19") (pin "7") (pinfunction "PRE_7") (pintype "input"))
    )
    (net (code "64") (name "Net-(U19-VSADJ)") (class "Default")
      (node (ref "R152") (pin "2") (pinfunction "2_2") (pintype "passive"))
      (node (ref "U19") (pin "30") (pinfunction "VSADJ_30") (pintype "input"))
    )
    (net (code "65") (name "Net-(U19-~{OE})") (class "Default")
      (node (ref "R157") (pin "2") (pinfunction "2_2") (pintype "passive"))
      (node (ref "U19") (pin "6") (pinfunction "~{OE}_6") (pintype "input"))
    )
    (net (code "66") (name "Net-(U21-COMP)") (class "Default")
      (node (ref "C180") (pin "2") (pinfunction "2_2") (pintype "passive"))
      (node (ref "U21") (pin "21") (pinfunction "COMP_21") (pintype "passive"))
    )
    (net (code "67") (name "VCC3V3") (class "Default")
      (node (ref "C167") (pin "1") (pinfunction "1_1") (pintype "passive"))
      (node (ref "C168") (pin "1") (pinfunction "1_1") (pintype "passive"))
      (node (ref "C169") (pin "1") (pinfunction "1_1") (pintype "passive"))
      (node (ref "C170") (pin "1") (pinfunction "1_1") (pintype "passive"))
      (node (ref "C171") (pin "1") (pinfunction "1_1") (pintype "passive"))
      (node (ref "C172") (pin "1") (pinfunction "1_1") (pintype "passive"))
      (node (ref "C173") (pin "1") (pinfunction "1_1") (pintype "passive"))
      (node (ref "C183") (pin "1") (pinfunction "1_1") (pintype "passive"))
      (node (ref "D37") (pin "2") (pinfunction "2_2") (pintype "passive"))
      (node (ref "L13") (pin "1") (pinfunction "1_1") (pintype "passive"))
      (node (ref "R155") (pin "2") (pinfunction "2_2") (pintype "passive"))
      (node (ref "R158") (pin "1") (pinfunction "1_1") (pintype "passive"))
      (node (ref "R159") (pin "1") (pinfunction "1_1") (pintype "passive"))
      (node (ref "R160") (pin "1") (pinfunction "1_1") (pintype "passive"))
      (node (ref "R163") (pin "1") (pinfunction "1_1") (pintype "passive"))
      (node (ref "R164") (pin "1") (pinfunction "1_1") (pintype "passive"))
      (node (ref "R168") (pin "2") (pinfunction "2_2") (pintype "passive"))
      (node (ref "R169") (pin "2") (pinfunction "2_2") (pintype "passive"))
      (node (ref "U19") (pin "11") (pinfunction "VCC_11") (pintype "power_in"))
      (node (ref "U19") (pin "17") (pinfunction "VCC_17") (pintype "power_in"))
      (node (ref "U19") (pin "24") (pinfunction "VCC_24") (pintype "power_in"))
      (node (ref "U19") (pin "27") (pinfunction "VCC_27") (pintype "power_in"))
      (node (ref "U19") (pin "34") (pinfunction "VCC_34") (pintype "power_in"))
      (node (ref "U19") (pin "4") (pinfunction "VCC_4") (pintype "power_in"))
      (node (ref "U19") (pin "40") (pinfunction "VCC_40") (pintype "power_in"))
      (node (ref "U21") (pin "33") (pinfunction "VREF_OUT_33") (pintype "passive"))
    )
    (net (code "68") (name "VCC5V") (class "Default")
      (node (ref "C174") (pin "2") (pinfunction "2_2") (pintype "passive"))
      (node (ref "C176") (pin "2") (pinfunction "2_2") (pintype "passive"))
      (node (ref "D50") (pin "2") (pinfunction "2_2") (pintype "passive"))
      (node (ref "U20") (pin "2") (pinfunction "IN_2") (pintype "power_in"))
      (node (ref "U20") (pin "3") (pinfunction "EN_3") (pintype "power_in"))
    )
    (net (code "69") (name "VCC5V0_RX") (class "Default")
      (node (ref "C178") (pin "2") (pinfunction "2_2") (pintype "passive"))
      (node (ref "D49") (pin "2") (pinfunction "2_2") (pintype "passive"))
      (node (ref "D51") (pin "2") (pinfunction "2_2") (pintype "passive"))
      (node (ref "J24") (pin "18") (pinfunction "+5V_Power_18") (pintype "passive"))
      (node (ref "R166") (pin "2") (pinfunction "2_2") (pintype "passive"))
      (node (ref "R167") (pin "2") (pinfunction "2_2") (pintype "passive"))
      (node (ref "R171") (pin "2") (pinfunction "2_2") (pintype "passive"))
      (node (ref "R172") (pin "2") (pinfunction "2_2") (pintype "passive"))
    )
    (net (code "70") (name "unconnected-(J23-Utility_{slash}_HEAC+-Pad14)") (class "Default")
      (node (ref "J23") (pin "14") (pinfunction "Utility_/_HEAC+_14") (pintype "passive"))
    )
    (net (code "71") (name "unconnected-(J24-Utility_{slash}_HEAC+-Pad14)") (class "Default")
      (node (ref "J24") (pin "14") (pinfunction "Utility_/_HEAC+_14") (pintype "passive"))
    )
    (net (code "72") (name "unconnected-(U20-NC-Pad4)") (class "Default")
      (node (ref "U20") (pin "4") (pinfunction "NC_4") (pintype "power_in"))
    )
  )
)
